# DG5v2_0_3.net
KiCad netlist of a schematic drawn in EAGLE
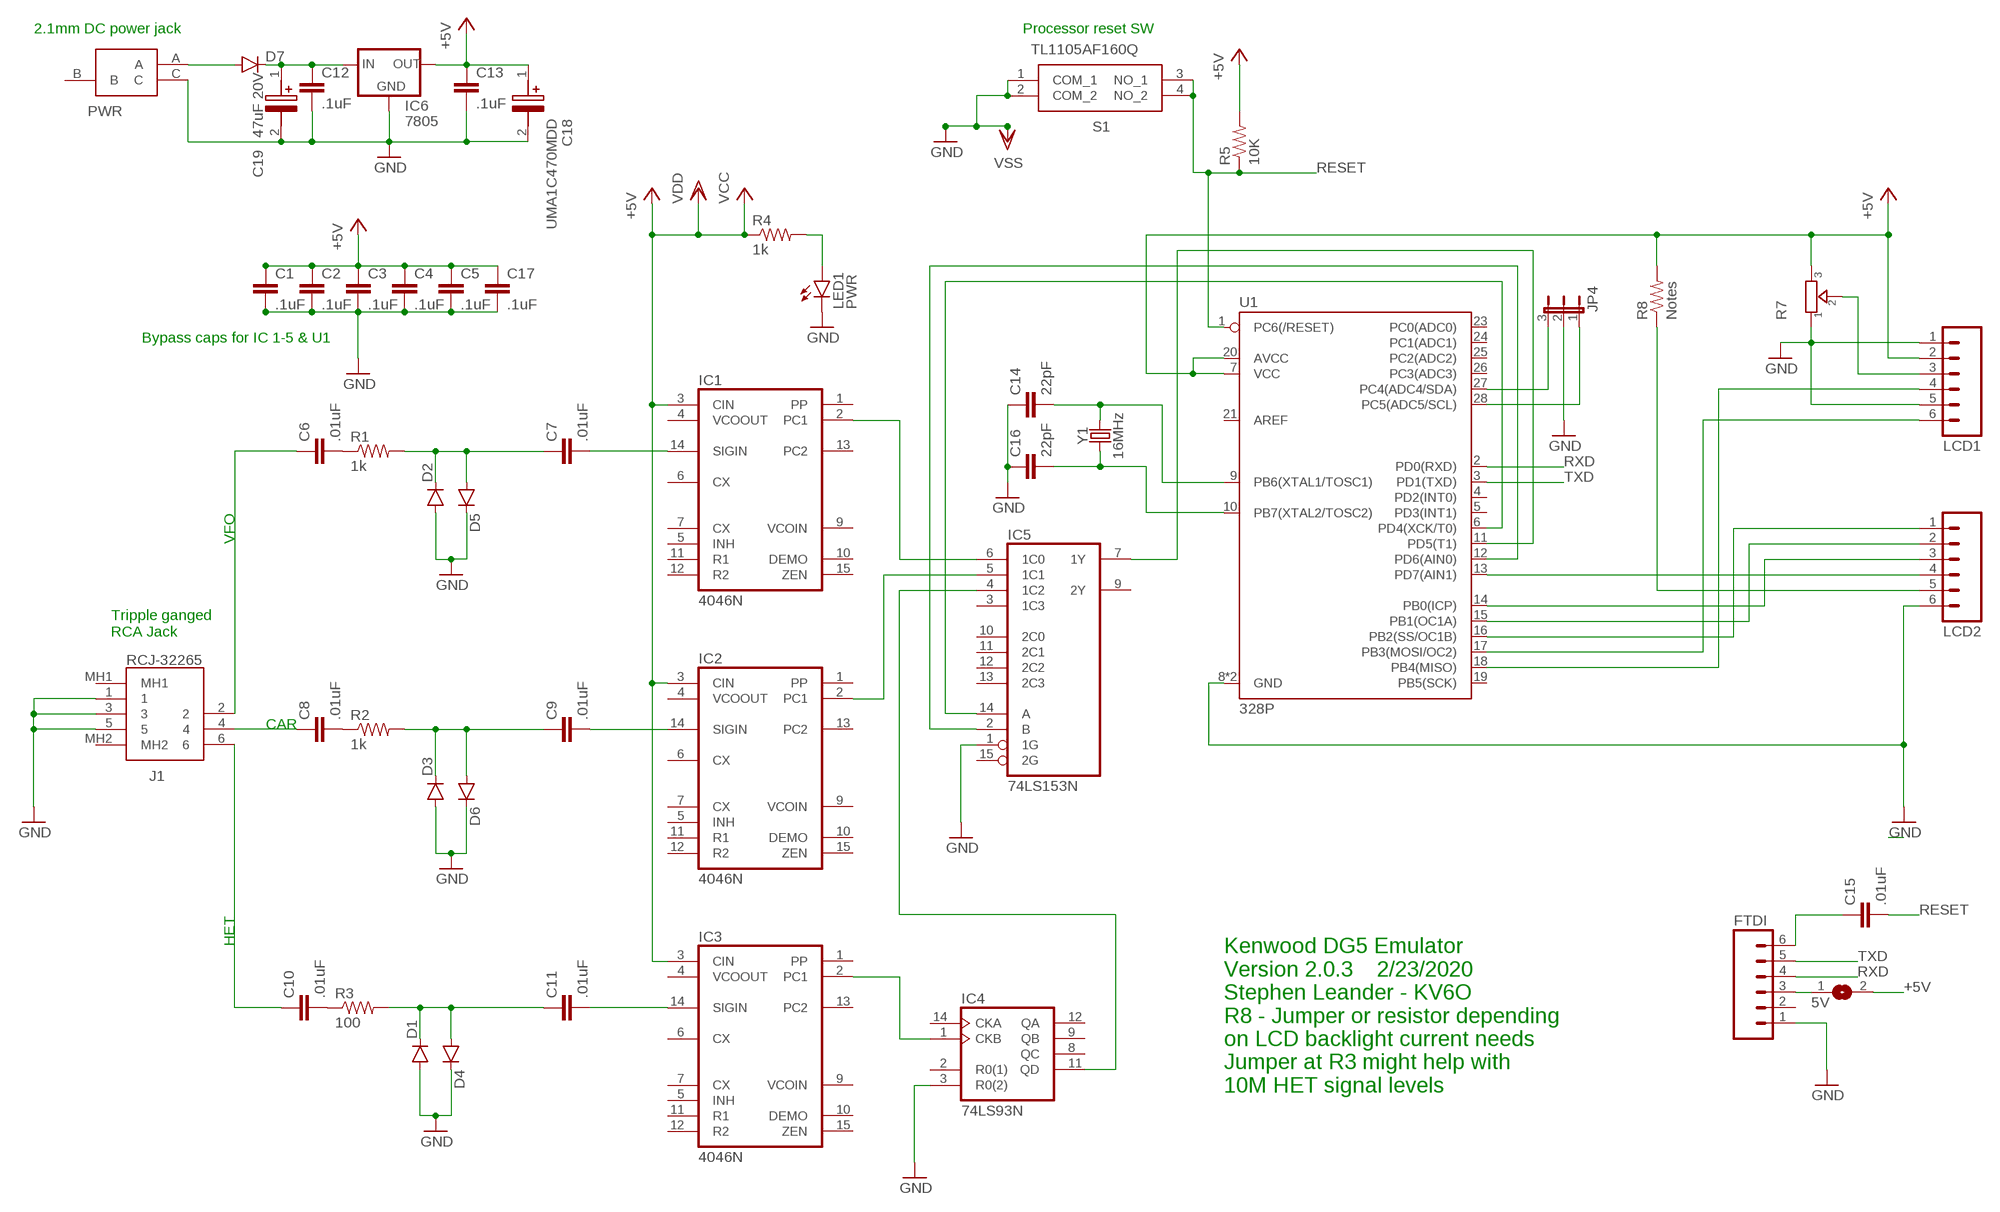
[diagram p0: schematic, sheet 1]

(export (version "E")
  (design (tool "Eeschema 10.0.6"))
  (components
    (comp (ref "5V") (value "SJ") (footprint "eagle-import:SJ") (libsource (lib "eagle-import") (part "SJ")))
    (comp (ref "C1")
      (value ".1uF")
      (footprint "eagle-import:CAP-PTH-SMALL-KIT")
      (libsource (lib "eagle-import") (part "CAPKIT"))
    )
    (comp (ref "C2")
      (value ".1uF")
      (footprint "eagle-import:CAP-PTH-SMALL-KIT")
      (libsource (lib "eagle-import") (part "CAPKIT"))
    )
    (comp (ref "C3")
      (value ".1uF")
      (footprint "eagle-import:CAP-PTH-SMALL-KIT")
      (libsource (lib "eagle-import") (part "CAPKIT"))
    )
    (comp (ref "C4")
      (value ".1uF")
      (footprint "eagle-import:CAP-PTH-SMALL-KIT")
      (libsource (lib "eagle-import") (part "CAPKIT"))
    )
    (comp (ref "C5")
      (value ".1uF")
      (footprint "eagle-import:CAP-PTH-SMALL-KIT")
      (libsource (lib "eagle-import") (part "CAPKIT"))
    )
    (comp (ref "C6")
      (value ".01uF")
      (footprint "eagle-import:CAP-PTH-SMALL-KIT")
      (libsource (lib "eagle-import") (part "CAPKIT"))
    )
    (comp (ref "C7")
      (value ".01uF")
      (footprint "eagle-import:CAP-PTH-SMALL-KIT")
      (libsource (lib "eagle-import") (part "CAPKIT"))
    )
    (comp (ref "C8")
      (value ".01uF")
      (footprint "eagle-import:CAP-PTH-SMALL-KIT")
      (libsource (lib "eagle-import") (part "CAPKIT"))
    )
    (comp (ref "C9")
      (value ".01uF")
      (footprint "eagle-import:CAP-PTH-SMALL-KIT")
      (libsource (lib "eagle-import") (part "CAPKIT"))
    )
    (comp (ref "C10")
      (value ".01uF")
      (footprint "eagle-import:CAP-PTH-SMALL-KIT")
      (libsource (lib "eagle-import") (part "CAPKIT"))
    )
    (comp (ref "C11")
      (value ".01uF")
      (footprint "eagle-import:CAP-PTH-SMALL-KIT")
      (libsource (lib "eagle-import") (part "CAPKIT"))
    )
    (comp (ref "C12")
      (value ".1uF")
      (footprint "eagle-import:CAP-PTH-SMALL-KIT")
      (libsource (lib "eagle-import") (part "CAPKIT"))
    )
    (comp (ref "C13")
      (value ".1uF")
      (footprint "eagle-import:CAP-PTH-SMALL-KIT")
      (libsource (lib "eagle-import") (part "CAPKIT"))
    )
    (comp (ref "C14")
      (value "22pF")
      (footprint "eagle-import:CAP-PTH-SMALL")
      (libsource (lib "eagle-import") (part "CAPPTH"))
    )
    (comp (ref "C15")
      (value ".01uF")
      (footprint "eagle-import:CAP-PTH-SMALL-KIT")
      (libsource (lib "eagle-import") (part "CAPKIT"))
    )
    (comp (ref "C16")
      (value "22pF")
      (footprint "eagle-import:CAP-PTH-SMALL")
      (libsource (lib "eagle-import") (part "CAPPTH"))
    )
    (comp (ref "C17")
      (value ".1uF")
      (footprint "eagle-import:CAP-PTH-SMALL-KIT")
      (libsource (lib "eagle-import") (part "CAPKIT"))
    )
    (comp (ref "C18")
      (value "UMA1C470MDD")
      (footprint "eagle-import:CAPPRD250W45D680H600")
      (fields (field (name "MOUSER_PART_NUMBER") "647-UMA1C470MDD"))
      (libsource (lib "eagle-import") (part "UMA1C470MDD"))
    )
    (comp (ref "C19")
      (value "47uF 20V")
      (footprint "eagle-import:CAPPRD250W45D680H600")
      (fields
        (field (name "MANUFACTURER_PART_NUMBER") "UMA1C470MDD")
        (field (name "MOUSER_PART_NUMBER") "647-UMA1C470MDD")
      )
      (libsource (lib "eagle-import") (part "UMA1C470MDD"))
    )
    (comp (ref "D1")
      (value "DIODE1N4148")
      (footprint "eagle-import:DIODE-1N4148")
      (libsource (lib "eagle-import") (part "DIODE1N4148"))
    )
    (comp (ref "D2")
      (value "DIODE1N4148")
      (footprint "eagle-import:DIODE-1N4148")
      (libsource (lib "eagle-import") (part "DIODE1N4148"))
    )
    (comp (ref "D3")
      (value "DIODE1N4148")
      (footprint "eagle-import:DIODE-1N4148")
      (libsource (lib "eagle-import") (part "DIODE1N4148"))
    )
    (comp (ref "D4")
      (value "DIODE1N4148")
      (footprint "eagle-import:DIODE-1N4148")
      (libsource (lib "eagle-import") (part "DIODE1N4148"))
    )
    (comp (ref "D5")
      (value "DIODE1N4148")
      (footprint "eagle-import:DIODE-1N4148")
      (libsource (lib "eagle-import") (part "DIODE1N4148"))
    )
    (comp (ref "D6")
      (value "DIODE1N4148")
      (footprint "eagle-import:DIODE-1N4148")
      (libsource (lib "eagle-import") (part "DIODE1N4148"))
    )
    (comp (ref "D7")
      (value "DIODE")
      (footprint "eagle-import:DIODE-1N4001-KIT")
      (libsource (lib "eagle-import") (part "DIODE"))
    )
    (comp (ref "FTDI")
      (value "M06SIP")
      (footprint "eagle-import:1X06")
      (libsource (lib "eagle-import") (part "M06SIP"))
    )
    (comp (ref "IC1")
      (value "4046N")
      (footprint "eagle-import:DIL16")
      (libsource (lib "eagle-import") (part "4046N"))
    )
    (comp (ref "IC2")
      (value "4046N")
      (footprint "eagle-import:DIL16")
      (libsource (lib "eagle-import") (part "4046N"))
    )
    (comp (ref "IC3")
      (value "4046N")
      (footprint "eagle-import:DIL16")
      (libsource (lib "eagle-import") (part "4046N"))
    )
    (comp (ref "IC4")
      (value "74LS93N")
      (footprint "eagle-import:DIL14")
      (libsource (lib "eagle-import") (part "7493NLS"))
    )
    (comp (ref "IC5")
      (value "74LS153N")
      (footprint "eagle-import:DIL16")
      (libsource (lib "eagle-import") (part "74153NLS"))
    )
    (comp (ref "IC6")
      (value "7805")
      (footprint "eagle-import:TO220-IGO")
      (libsource (lib "eagle-import") (part "V_REG_78XXSINK"))
    )
    (comp (ref "J1")
      (value "RCJ-32265")
      (footprint "eagle-import:RCJ32265")
      (fields (field (name "MOUSER_PART_NUMBER") "490-RCJ-32265"))
      (libsource (lib "eagle-import") (part "RCJ-32265"))
    )
    (comp (ref "JP4")
      (value "JP2E")
      (footprint "eagle-import:JP2")
      (libsource (lib "eagle-import") (part "JP2E"))
    )
    (comp (ref "LCD1")
      (value "M06SIP")
      (footprint "eagle-import:1X06")
      (libsource (lib "eagle-import") (part "M06SIP"))
    )
    (comp (ref "LCD2")
      (value "M06SIP")
      (footprint "eagle-import:1X06")
      (libsource (lib "eagle-import") (part "M06SIP"))
    )
    (comp (ref "LED1")
      (value "PWR")
      (footprint "eagle-import:LED3MM")
      (fields (field (name "MF") "VISHAY SEMICONDUCTOR"))
      (libsource (lib "eagle-import") (part "TLLG4400"))
    )
    (comp (ref "PWR")
      (value "163-179PH-EX")
      (footprint "eagle-import:163179PHEX")
      (libsource (lib "eagle-import") (part "163-179PH-EX"))
    )
    (comp (ref "R1")
      (value "1k")
      (footprint "eagle-import:1_6W-RES")
      (libsource (lib "eagle-import") (part "RESISTORPTH-1/6W"))
    )
    (comp (ref "R2")
      (value "1k")
      (footprint "eagle-import:1_6W-RES")
      (libsource (lib "eagle-import") (part "RESISTORPTH-1/6W"))
    )
    (comp (ref "R3")
      (value "100")
      (footprint "eagle-import:1_6W-RES")
      (libsource (lib "eagle-import") (part "RESISTORPTH-1/6W"))
    )
    (comp (ref "R4")
      (value "1k")
      (footprint "eagle-import:1_6W-RES")
      (libsource (lib "eagle-import") (part "RESISTORPTH-1/6W"))
    )
    (comp (ref "R5")
      (value "10K")
      (footprint "eagle-import:1_6W-RES")
      (libsource (lib "eagle-import") (part "RESISTORPTH-1/6W"))
    )
    (comp (ref "R7")
      (value "TRIMMER-3306F")
      (footprint "eagle-import:TRIMMER_3306F")
      (libsource (lib "eagle-import") (part "TRIMMER-3306F"))
    )
    (comp (ref "R8")
      (value "Notes")
      (footprint "eagle-import:1_6W-RES")
      (libsource (lib "eagle-import") (part "RESISTORPTH-1/6W"))
    )
    (comp (ref "S1")
      (value "TL1105AF160Q")
      (footprint "eagle-import:TL1105AF160Q")
      (fields (field (name "MOUSER_PART_NUMBER") "612-TL1105A"))
      (libsource (lib "eagle-import") (part "TL1105AF160Q"))
    )
    (comp (ref "U1")
      (value "328P")
      (footprint "eagle-import:DIP28")
      (libsource (lib "eagle-import") (part "ATMEGA328P_PDIP"))
    )
    (comp (ref "Y1")
      (value "16MHz")
      (footprint "eagle-import:HC49US")
      (libsource (lib "eagle-import") (part "CRYSTAL-16MHZPTH-HC49US"))
    )
  )
  (nets
    (net (code "1") (name "+5V") (class "Default")
      (node (ref "5V") (pin "2") (pinfunction "2_2") (pintype "passive"))
      (node (ref "C1") (pin "1") (pinfunction "1_1") (pintype "passive"))
      (node (ref "C13") (pin "1") (pinfunction "1_1") (pintype "passive"))
      (node (ref "C17") (pin "1") (pinfunction "1_1") (pintype "passive"))
      (node (ref "C18") (pin "1") (pinfunction "+_1") (pintype "bidirectional"))
      (node (ref "C2") (pin "1") (pinfunction "1_1") (pintype "passive"))
      (node (ref "C3") (pin "1") (pinfunction "1_1") (pintype "passive"))
      (node (ref "C4") (pin "1") (pinfunction "1_1") (pintype "passive"))
      (node (ref "C5") (pin "1") (pinfunction "1_1") (pintype "passive"))
      (node (ref "IC1") (pin "3") (pinfunction "CIN_3") (pintype "input"))
      (node (ref "IC2") (pin "3") (pinfunction "CIN_3") (pintype "input"))
      (node (ref "IC3") (pin "3") (pinfunction "CIN_3") (pintype "input"))
      (node (ref "IC6") (pin "OUT") (pinfunction "OUT_OUT") (pintype "output"))
      (node (ref "LCD1") (pin "2") (pinfunction "2_2") (pintype "passive"))
      (node (ref "R4") (pin "1") (pinfunction "1_1") (pintype "passive"))
      (node (ref "R5") (pin "2") (pinfunction "2_2") (pintype "passive"))
      (node (ref "R7") (pin "3") (pinfunction "3_3") (pintype "passive"))
      (node (ref "R8") (pin "2") (pinfunction "2_2") (pintype "passive"))
      (node (ref "U1") (pin "20") (pinfunction "AVCC_20") (pintype "bidirectional"))
      (node (ref "U1") (pin "7") (pinfunction "VCC_7") (pintype "bidirectional"))
    )
    (net (code "2") (name "/RESET") (class "Default")
      (node (ref "C15") (pin "2") (pinfunction "2_2") (pintype "passive"))
      (node (ref "R5") (pin "1") (pinfunction "1_1") (pintype "passive"))
      (node (ref "S1") (pin "3") (pinfunction "NO_1_3") (pintype "bidirectional"))
      (node (ref "S1") (pin "4") (pinfunction "NO_2_4") (pintype "bidirectional"))
      (node (ref "U1") (pin "1") (pinfunction "PC6(/RESET)_1") (pintype "bidirectional"))
    )
    (net (code "3") (name "/RXD") (class "Default")
      (node (ref "FTDI") (pin "4") (pinfunction "4_4") (pintype "passive"))
      (node (ref "U1") (pin "2") (pinfunction "PD0(RXD)_2") (pintype "bidirectional"))
    )
    (net (code "4") (name "/TXD") (class "Default")
      (node (ref "FTDI") (pin "5") (pinfunction "5_5") (pintype "passive"))
      (node (ref "U1") (pin "3") (pinfunction "PD1(TXD)_3") (pintype "bidirectional"))
    )
    (net (code "5") (name "GND") (class "Default")
      (node (ref "C1") (pin "2") (pinfunction "2_2") (pintype "passive"))
      (node (ref "C12") (pin "2") (pinfunction "2_2") (pintype "passive"))
      (node (ref "C13") (pin "2") (pinfunction "2_2") (pintype "passive"))
      (node (ref "C14") (pin "1") (pinfunction "1_1") (pintype "passive"))
      (node (ref "C16") (pin "1") (pinfunction "1_1") (pintype "passive"))
      (node (ref "C17") (pin "2") (pinfunction "2_2") (pintype "passive"))
      (node (ref "C18") (pin "2") (pinfunction "-_2") (pintype "bidirectional"))
      (node (ref "C19") (pin "2") (pinfunction "-_2") (pintype "bidirectional"))
      (node (ref "C2") (pin "2") (pinfunction "2_2") (pintype "passive"))
      (node (ref "C3") (pin "2") (pinfunction "2_2") (pintype "passive"))
      (node (ref "C4") (pin "2") (pinfunction "2_2") (pintype "passive"))
      (node (ref "C5") (pin "2") (pinfunction "2_2") (pintype "passive"))
      (node (ref "D1") (pin "A") (pinfunction "A_A") (pintype "passive"))
      (node (ref "D2") (pin "A") (pinfunction "A_A") (pintype "passive"))
      (node (ref "D3") (pin "A") (pinfunction "A_A") (pintype "passive"))
      (node (ref "D4") (pin "C") (pinfunction "C_C") (pintype "passive"))
      (node (ref "D5") (pin "C") (pinfunction "C_C") (pintype "passive"))
      (node (ref "D6") (pin "C") (pinfunction "C_C") (pintype "passive"))
      (node (ref "FTDI") (pin "1") (pinfunction "1_1") (pintype "passive"))
      (node (ref "IC4") (pin "3") (pinfunction "R0(2)_3") (pintype "input"))
      (node (ref "IC5") (pin "1") (pinfunction "1G_1") (pintype "input"))
      (node (ref "IC6") (pin "GND") (pinfunction "GND_GND") (pintype "input"))
      (node (ref "J1") (pin "1") (pinfunction "1_1") (pintype "bidirectional"))
      (node (ref "J1") (pin "3") (pinfunction "3_3") (pintype "bidirectional"))
      (node (ref "J1") (pin "5") (pinfunction "5_5") (pintype "bidirectional"))
      (node (ref "JP4") (pin "2") (pinfunction "2_2") (pintype "passive"))
      (node (ref "LCD1") (pin "1") (pinfunction "1_1") (pintype "passive"))
      (node (ref "LCD1") (pin "5") (pinfunction "5_5") (pintype "passive"))
      (node (ref "LCD2") (pin "6") (pinfunction "6_6") (pintype "passive"))
      (node (ref "LED1") (pin "K") (pinfunction "C_K") (pintype "passive"))
      (node (ref "PWR") (pin "C") (pinfunction "C_C") (pintype "bidirectional"))
      (node (ref "R7") (pin "1") (pinfunction "1_1") (pintype "passive"))
      (node (ref "S1") (pin "1") (pinfunction "COM_1_1") (pintype "bidirectional"))
      (node (ref "S1") (pin "2") (pinfunction "COM_2_2") (pintype "bidirectional"))
      (node (ref "U1") (pin "22") (pinfunction "GND_22") (pintype "bidirectional"))
      (node (ref "U1") (pin "8") (pinfunction "GND_8") (pintype "bidirectional"))
    )
    (net (code "6") (name "Net-(5V-Pad1)") (class "Default")
      (node (ref "5V") (pin "1") (pinfunction "1_1") (pintype "passive"))
      (node (ref "FTDI") (pin "3") (pinfunction "3_3") (pintype "passive"))
    )
    (net (code "7") (name "Net-(C6-Pad1)") (class "Default")
      (node (ref "C6") (pin "1") (pinfunction "1_1") (pintype "passive"))
      (node (ref "J1") (pin "2") (pinfunction "2_2") (pintype "bidirectional"))
    )
    (net (code "8") (name "Net-(C6-Pad2)") (class "Default")
      (node (ref "C6") (pin "2") (pinfunction "2_2") (pintype "passive"))
      (node (ref "R1") (pin "1") (pinfunction "1_1") (pintype "passive"))
    )
    (net (code "9") (name "Net-(C7-Pad1)") (class "Default")
      (node (ref "C7") (pin "1") (pinfunction "1_1") (pintype "passive"))
      (node (ref "D2") (pin "C") (pinfunction "C_C") (pintype "passive"))
      (node (ref "D5") (pin "A") (pinfunction "A_A") (pintype "passive"))
      (node (ref "R1") (pin "2") (pinfunction "2_2") (pintype "passive"))
    )
    (net (code "10") (name "Net-(C8-Pad1)") (class "Default")
      (node (ref "C8") (pin "1") (pinfunction "1_1") (pintype "passive"))
      (node (ref "J1") (pin "4") (pinfunction "4_4") (pintype "bidirectional"))
    )
    (net (code "11") (name "Net-(C8-Pad2)") (class "Default")
      (node (ref "C8") (pin "2") (pinfunction "2_2") (pintype "passive"))
      (node (ref "R2") (pin "1") (pinfunction "1_1") (pintype "passive"))
    )
    (net (code "12") (name "Net-(C9-Pad1)") (class "Default")
      (node (ref "C9") (pin "1") (pinfunction "1_1") (pintype "passive"))
      (node (ref "D3") (pin "C") (pinfunction "C_C") (pintype "passive"))
      (node (ref "D6") (pin "A") (pinfunction "A_A") (pintype "passive"))
      (node (ref "R2") (pin "2") (pinfunction "2_2") (pintype "passive"))
    )
    (net (code "13") (name "Net-(C10-Pad1)") (class "Default")
      (node (ref "C10") (pin "1") (pinfunction "1_1") (pintype "passive"))
      (node (ref "J1") (pin "6") (pinfunction "6_6") (pintype "bidirectional"))
    )
    (net (code "14") (name "Net-(C10-Pad2)") (class "Default")
      (node (ref "C10") (pin "2") (pinfunction "2_2") (pintype "passive"))
      (node (ref "R3") (pin "1") (pinfunction "1_1") (pintype "passive"))
    )
    (net (code "15") (name "Net-(C11-Pad1)") (class "Default")
      (node (ref "C11") (pin "1") (pinfunction "1_1") (pintype "passive"))
      (node (ref "D1") (pin "C") (pinfunction "C_C") (pintype "passive"))
      (node (ref "D4") (pin "A") (pinfunction "A_A") (pintype "passive"))
      (node (ref "R3") (pin "2") (pinfunction "2_2") (pintype "passive"))
    )
    (net (code "16") (name "Net-(C15-Pad1)") (class "Default")
      (node (ref "C15") (pin "1") (pinfunction "1_1") (pintype "passive"))
      (node (ref "FTDI") (pin "6") (pinfunction "6_6") (pintype "passive"))
    )
    (net (code "17") (name "Net-(C19-+)") (class "Default")
      (node (ref "C12") (pin "1") (pinfunction "1_1") (pintype "passive"))
      (node (ref "C19") (pin "1") (pinfunction "+_1") (pintype "bidirectional"))
      (node (ref "D7") (pin "C") (pinfunction "C_C") (pintype "passive"))
      (node (ref "IC6") (pin "IN") (pinfunction "IN_IN") (pintype "input"))
    )
    (net (code "18") (name "Net-(D7-PadA)") (class "Default")
      (node (ref "D7") (pin "A") (pinfunction "A_A") (pintype "passive"))
      (node (ref "PWR") (pin "A") (pinfunction "A_A") (pintype "bidirectional"))
    )
    (net (code "19") (name "Net-(IC1A-PC1)") (class "Default")
      (node (ref "IC1") (pin "2") (pinfunction "PC1_2") (pintype "output"))
      (node (ref "IC5") (pin "6") (pinfunction "1C0_6") (pintype "input"))
    )
    (net (code "20") (name "Net-(IC1A-SIGIN)") (class "Default")
      (node (ref "C7") (pin "2") (pinfunction "2_2") (pintype "passive"))
      (node (ref "IC1") (pin "14") (pinfunction "SIGIN_14") (pintype "input"))
    )
    (net (code "21") (name "Net-(IC2A-PC1)") (class "Default")
      (node (ref "IC2") (pin "2") (pinfunction "PC1_2") (pintype "output"))
      (node (ref "IC5") (pin "5") (pinfunction "1C1_5") (pintype "input"))
    )
    (net (code "22") (name "Net-(IC2A-SIGIN)") (class "Default")
      (node (ref "C9") (pin "2") (pinfunction "2_2") (pintype "passive"))
      (node (ref "IC2") (pin "14") (pinfunction "SIGIN_14") (pintype "input"))
    )
    (net (code "23") (name "Net-(IC3A-PC1)") (class "Default")
      (node (ref "IC3") (pin "2") (pinfunction "PC1_2") (pintype "output"))
      (node (ref "IC4") (pin "1") (pinfunction "CKB_1") (pintype "input"))
    )
    (net (code "24") (name "Net-(IC3A-SIGIN)") (class "Default")
      (node (ref "C11") (pin "2") (pinfunction "2_2") (pintype "passive"))
      (node (ref "IC3") (pin "14") (pinfunction "SIGIN_14") (pintype "input"))
    )
    (net (code "25") (name "Net-(IC4A-QD)") (class "Default")
      (node (ref "IC4") (pin "11") (pinfunction "QD_11") (pintype "output"))
      (node (ref "IC5") (pin "4") (pinfunction "1C2_4") (pintype "input"))
    )
    (net (code "26") (name "Net-(IC5A-1Y)") (class "Default")
      (node (ref "IC5") (pin "7") (pinfunction "1Y_7") (pintype "output"))
      (node (ref "U1") (pin "11") (pinfunction "PD5(T1)_11") (pintype "bidirectional"))
    )
    (net (code "27") (name "Net-(IC5A-A)") (class "Default")
      (node (ref "IC5") (pin "14") (pinfunction "A_14") (pintype "input"))
      (node (ref "U1") (pin "6") (pinfunction "PD4(XCK/T0)_6") (pintype "bidirectional"))
    )
    (net (code "28") (name "Net-(IC5A-B)") (class "Default")
      (node (ref "IC5") (pin "2") (pinfunction "B_2") (pintype "input"))
      (node (ref "U1") (pin "12") (pinfunction "PD6(AIN0)_12") (pintype "bidirectional"))
    )
    (net (code "29") (name "Net-(LCD1-Pad3)") (class "Default")
      (node (ref "LCD1") (pin "3") (pinfunction "3_3") (pintype "passive"))
      (node (ref "R7") (pin "2") (pinfunction "2_2") (pintype "passive"))
    )
    (net (code "30") (name "Net-(LCD2-Pad5)") (class "Default")
      (node (ref "LCD2") (pin "5") (pinfunction "5_5") (pintype "passive"))
      (node (ref "R8") (pin "1") (pinfunction "1_1") (pintype "passive"))
    )
    (net (code "31") (name "Net-(LED1-PadA)") (class "Default")
      (node (ref "LED1") (pin "A") (pinfunction "A_A") (pintype "passive"))
      (node (ref "R4") (pin "2") (pinfunction "2_2") (pintype "passive"))
    )
    (net (code "32") (name "Net-(U1-PB0(ICP))") (class "Default")
      (node (ref "LCD2") (pin "3") (pinfunction "3_3") (pintype "passive"))
      (node (ref "U1") (pin "14") (pinfunction "PB0(ICP)_14") (pintype "bidirectional"))
    )
    (net (code "33") (name "Net-(U1-PB1(OC1A))") (class "Default")
      (node (ref "LCD2") (pin "2") (pinfunction "2_2") (pintype "passive"))
      (node (ref "U1") (pin "15") (pinfunction "PB1(OC1A)_15") (pintype "bidirectional"))
    )
    (net (code "34") (name "Net-(U1-PB2(SS{slash}OC1B))") (class "Default")
      (node (ref "LCD2") (pin "1") (pinfunction "1_1") (pintype "passive"))
      (node (ref "U1") (pin "16") (pinfunction "PB2(SS/OC1B)_16") (pintype "bidirectional"))
    )
    (net (code "35") (name "Net-(U1-PB3(MOSI{slash}OC2))") (class "Default")
      (node (ref "LCD1") (pin "6") (pinfunction "6_6") (pintype "passive"))
      (node (ref "U1") (pin "17") (pinfunction "PB3(MOSI/OC2)_17") (pintype "bidirectional"))
    )
    (net (code "36") (name "Net-(U1-PB4(MISO))") (class "Default")
      (node (ref "LCD1") (pin "4") (pinfunction "4_4") (pintype "passive"))
      (node (ref "U1") (pin "18") (pinfunction "PB4(MISO)_18") (pintype "bidirectional"))
    )
    (net (code "37") (name "Net-(U1-PB6(XTAL1{slash}TOSC1))") (class "Default")
      (node (ref "C14") (pin "2") (pinfunction "2_2") (pintype "passive"))
      (node (ref "U1") (pin "9") (pinfunction "PB6(XTAL1/TOSC1)_9") (pintype "bidirectional"))
      (node (ref "Y1") (pin "2") (pinfunction "2_2") (pintype "passive"))
    )
    (net (code "38") (name "Net-(U1-PB7(XTAL2{slash}TOSC2))") (class "Default")
      (node (ref "C16") (pin "2") (pinfunction "2_2") (pintype "passive"))
      (node (ref "U1") (pin "10") (pinfunction "PB7(XTAL2/TOSC2)_10") (pintype "bidirectional"))
      (node (ref "Y1") (pin "1") (pinfunction "1_1") (pintype "passive"))
    )
    (net (code "39") (name "Net-(U1-PC4(ADC4{slash}SDA))") (class "Default")
      (node (ref "JP4") (pin "3") (pinfunction "3_3") (pintype "passive"))
      (node (ref "U1") (pin "27") (pinfunction "PC4(ADC4/SDA)_27") (pintype "bidirectional"))
    )
    (net (code "40") (name "Net-(U1-PC5(ADC5{slash}SCL))") (class "Default")
      (node (ref "JP4") (pin "1") (pinfunction "1_1") (pintype "passive"))
      (node (ref "U1") (pin "28") (pinfunction "PC5(ADC5/SCL)_28") (pintype "bidirectional"))
    )
    (net (code "41") (name "Net-(U1-PD7(AIN1))") (class "Default")
      (node (ref "LCD2") (pin "4") (pinfunction "4_4") (pintype "passive"))
      (node (ref "U1") (pin "13") (pinfunction "PD7(AIN1)_13") (pintype "bidirectional"))
    )
    (net (code "42") (name "unconnected-(FTDI-Pad2)") (class "Default")
      (node (ref "FTDI") (pin "2") (pinfunction "2_2") (pintype "passive"))
    )
    (net (code "43") (name "unconnected-(IC1A-CX-Pad6)") (class "Default")
      (node (ref "IC1") (pin "6") (pinfunction "CX_6") (pintype "input"))
    )
    (net (code "44") (name "unconnected-(IC1A-CX-Pad7)") (class "Default")
      (node (ref "IC1") (pin "7") (pinfunction "CX_7") (pintype "input"))
    )
    (net (code "45") (name "unconnected-(IC1A-DEMO-Pad10)") (class "Default")
      (node (ref "IC1") (pin "10") (pinfunction "DEMO_10") (pintype "output"))
    )
    (net (code "46") (name "unconnected-(IC1A-INH-Pad5)") (class "Default")
      (node (ref "IC1") (pin "5") (pinfunction "INH_5") (pintype "input"))
    )
    (net (code "47") (name "unconnected-(IC1A-PC2-Pad13)") (class "Default")
      (node (ref "IC1") (pin "13") (pinfunction "PC2_13") (pintype "output"))
    )
    (net (code "48") (name "unconnected-(IC1A-PP-Pad1)") (class "Default")
      (node (ref "IC1") (pin "1") (pinfunction "PP_1") (pintype "output"))
    )
    (net (code "49") (name "unconnected-(IC1A-R1-Pad11)") (class "Default")
      (node (ref "IC1") (pin "11") (pinfunction "R1_11") (pintype "input"))
    )
    (net (code "50") (name "unconnected-(IC1A-R2-Pad12)") (class "Default")
      (node (ref "IC1") (pin "12") (pinfunction "R2_12") (pintype "input"))
    )
    (net (code "51") (name "unconnected-(IC1A-VCOIN-Pad9)") (class "Default")
      (node (ref "IC1") (pin "9") (pinfunction "VCOIN_9") (pintype "input"))
    )
    (net (code "52") (name "unconnected-(IC1A-VCOOUT-Pad4)") (class "Default")
      (node (ref "IC1") (pin "4") (pinfunction "VCOOUT_4") (pintype "output"))
    )
    (net (code "53") (name "unconnected-(IC1A-ZEN-Pad15)") (class "Default")
      (node (ref "IC1") (pin "15") (pinfunction "ZEN_15") (pintype "input"))
    )
    (net (code "54") (name "unconnected-(IC2A-CX-Pad6)") (class "Default")
      (node (ref "IC2") (pin "6") (pinfunction "CX_6") (pintype "input"))
    )
    (net (code "55") (name "unconnected-(IC2A-CX-Pad7)") (class "Default")
      (node (ref "IC2") (pin "7") (pinfunction "CX_7") (pintype "input"))
    )
    (net (code "56") (name "unconnected-(IC2A-DEMO-Pad10)") (class "Default")
      (node (ref "IC2") (pin "10") (pinfunction "DEMO_10") (pintype "output"))
    )
    (net (code "57") (name "unconnected-(IC2A-INH-Pad5)") (class "Default")
      (node (ref "IC2") (pin "5") (pinfunction "INH_5") (pintype "input"))
    )
    (net (code "58") (name "unconnected-(IC2A-PC2-Pad13)") (class "Default")
      (node (ref "IC2") (pin "13") (pinfunction "PC2_13") (pintype "output"))
    )
    (net (code "59") (name "unconnected-(IC2A-PP-Pad1)") (class "Default")
      (node (ref "IC2") (pin "1") (pinfunction "PP_1") (pintype "output"))
    )
    (net (code "60") (name "unconnected-(IC2A-R1-Pad11)") (class "Default")
      (node (ref "IC2") (pin "11") (pinfunction "R1_11") (pintype "input"))
    )
    (net (code "61") (name "unconnected-(IC2A-R2-Pad12)") (class "Default")
      (node (ref "IC2") (pin "12") (pinfunction "R2_12") (pintype "input"))
    )
    (net (code "62") (name "unconnected-(IC2A-VCOIN-Pad9)") (class "Default")
      (node (ref "IC2") (pin "9") (pinfunction "VCOIN_9") (pintype "input"))
    )
    (net (code "63") (name "unconnected-(IC2A-VCOOUT-Pad4)") (class "Default")
      (node (ref "IC2") (pin "4") (pinfunction "VCOOUT_4") (pintype "output"))
    )
    (net (code "64") (name "unconnected-(IC2A-ZEN-Pad15)") (class "Default")
      (node (ref "IC2") (pin "15") (pinfunction "ZEN_15") (pintype "input"))
    )
    (net (code "65") (name "unconnected-(IC3A-CX-Pad6)") (class "Default")
      (node (ref "IC3") (pin "6") (pinfunction "CX_6") (pintype "input"))
    )
    (net (code "66") (name "unconnected-(IC3A-CX-Pad7)") (class "Default")
      (node (ref "IC3") (pin "7") (pinfunction "CX_7") (pintype "input"))
    )
    (net (code "67") (name "unconnected-(IC3A-DEMO-Pad10)") (class "Default")
      (node (ref "IC3") (pin "10") (pinfunction "DEMO_10") (pintype "output"))
    )
    (net (code "68") (name "unconnected-(IC3A-INH-Pad5)") (class "Default")
      (node (ref "IC3") (pin "5") (pinfunction "INH_5") (pintype "input"))
    )
    (net (code "69") (name "unconnected-(IC3A-PC2-Pad13)") (class "Default")
      (node (ref "IC3") (pin "13") (pinfunction "PC2_13") (pintype "output"))
    )
    (net (code "70") (name "unconnected-(IC3A-PP-Pad1)") (class "Default")
      (node (ref "IC3") (pin "1") (pinfunction "PP_1") (pintype "output"))
    )
    (net (code "71") (name "unconnected-(IC3A-R1-Pad11)") (class "Default")
      (node (ref "IC3") (pin "11") (pinfunction "R1_11") (pintype "input"))
    )
    (net (code "72") (name "unconnected-(IC3A-R2-Pad12)") (class "Default")
      (node (ref "IC3") (pin "12") (pinfunction "R2_12") (pintype "input"))
    )
    (net (code "73") (name "unconnected-(IC3A-VCOIN-Pad9)") (class "Default")
      (node (ref "IC3") (pin "9") (pinfunction "VCOIN_9") (pintype "input"))
    )
    (net (code "74") (name "unconnected-(IC3A-VCOOUT-Pad4)") (class "Default")
      (node (ref "IC3") (pin "4") (pinfunction "VCOOUT_4") (pintype "output"))
    )
    (net (code "75") (name "unconnected-(IC3A-ZEN-Pad15)") (class "Default")
      (node (ref "IC3") (pin "15") (pinfunction "ZEN_15") (pintype "input"))
    )
    (net (code "76") (name "unconnected-(IC4A-CKA-Pad14)") (class "Default")
      (node (ref "IC4") (pin "14") (pinfunction "CKA_14") (pintype "input"))
    )
    (net (code "77") (name "unconnected-(IC4A-QA-Pad12)") (class "Default")
      (node (ref "IC4") (pin "12") (pinfunction "QA_12") (pintype "output"))
    )
    (net (code "78") (name "unconnected-(IC4A-QB-Pad9)") (class "Default")
      (node (ref "IC4") (pin "9") (pinfunction "QB_9") (pintype "output"))
    )
    (net (code "79") (name "unconnected-(IC4A-QC-Pad8)") (class "Default")
      (node (ref "IC4") (pin "8") (pinfunction "QC_8") (pintype "output"))
    )
    (net (code "80") (name "unconnected-(IC4A-R0(1)-Pad2)") (class "Default")
      (node (ref "IC4") (pin "2") (pinfunction "R0(1)_2") (pintype "input"))
    )
    (net (code "81") (name "unconnected-(IC5A-1C3-Pad3)") (class "Default")
      (node (ref "IC5") (pin "3") (pinfunction "1C3_3") (pintype "input"))
    )
    (net (code "82") (name "unconnected-(IC5A-2C0-Pad10)") (class "Default")
      (node (ref "IC5") (pin "10") (pinfunction "2C0_10") (pintype "input"))
    )
    (net (code "83") (name "unconnected-(IC5A-2C1-Pad11)") (class "Default")
      (node (ref "IC5") (pin "11") (pinfunction "2C1_11") (pintype "input"))
    )
    (net (code "84") (name "unconnected-(IC5A-2C2-Pad12)") (class "Default")
      (node (ref "IC5") (pin "12") (pinfunction "2C2_12") (pintype "input"))
    )
    (net (code "85") (name "unconnected-(IC5A-2C3-Pad13)") (class "Default")
      (node (ref "IC5") (pin "13") (pinfunction "2C3_13") (pintype "input"))
    )
    (net (code "86") (name "unconnected-(IC5A-2G-Pad15)") (class "Default")
      (node (ref "IC5") (pin "15") (pinfunction "2G_15") (pintype "input"))
    )
    (net (code "87") (name "unconnected-(IC5A-2Y-Pad9)") (class "Default")
      (node (ref "IC5") (pin "9") (pinfunction "2Y_9") (pintype "output"))
    )
    (net (code "88") (name "unconnected-(J1-PadMH1)") (class "Default")
      (node (ref "J1") (pin "MH1") (pinfunction "MH1_MH1") (pintype "bidirectional"))
    )
    (net (code "89") (name "unconnected-(J1-PadMH2)") (class "Default")
      (node (ref "J1") (pin "MH2") (pinfunction "MH2_MH2") (pintype "bidirectional"))
    )
    (net (code "90") (name "unconnected-(PWR-PadB)") (class "Default")
      (node (ref "PWR") (pin "B") (pinfunction "B_B") (pintype "bidirectional"))
    )
    (net (code "91") (name "unconnected-(U1-AREF-Pad21)") (class "Default")
      (node (ref "U1") (pin "21") (pinfunction "AREF_21") (pintype "bidirectional"))
    )
    (net (code "92") (name "unconnected-(U1-PB5(SCK)-Pad19)") (class "Default")
      (node (ref "U1") (pin "19") (pinfunction "PB5(SCK)_19") (pintype "bidirectional"))
    )
    (net (code "93") (name "unconnected-(U1-PC0(ADC0)-Pad23)") (class "Default")
      (node (ref "U1") (pin "23") (pinfunction "PC0(ADC0)_23") (pintype "bidirectional"))
    )
    (net (code "94") (name "unconnected-(U1-PC1(ADC1)-Pad24)") (class "Default")
      (node (ref "U1") (pin "24") (pinfunction "PC1(ADC1)_24") (pintype "bidirectional"))
    )
    (net (code "95") (name "unconnected-(U1-PC2(ADC2)-Pad25)") (class "Default")
      (node (ref "U1") (pin "25") (pinfunction "PC2(ADC2)_25") (pintype "bidirectional"))
    )
    (net (code "96") (name "unconnected-(U1-PC3(ADC3)-Pad26)") (class "Default")
      (node (ref "U1") (pin "26") (pinfunction "PC3(ADC3)_26") (pintype "bidirectional"))
    )
    (net (code "97") (name "unconnected-(U1-PD2(INT0)-Pad4)") (class "Default")
      (node (ref "U1") (pin "4") (pinfunction "PD2(INT0)_4") (pintype "bidirectional"))
    )
    (net (code "98") (name "unconnected-(U1-PD3(INT1)-Pad5)") (class "Default")
      (node (ref "U1") (pin "5") (pinfunction "PD3(INT1)_5") (pintype "bidirectional"))
    )
  )
)
